# HUD-mohterboard.net
KiCad netlist of a schematic drawn in EAGLE
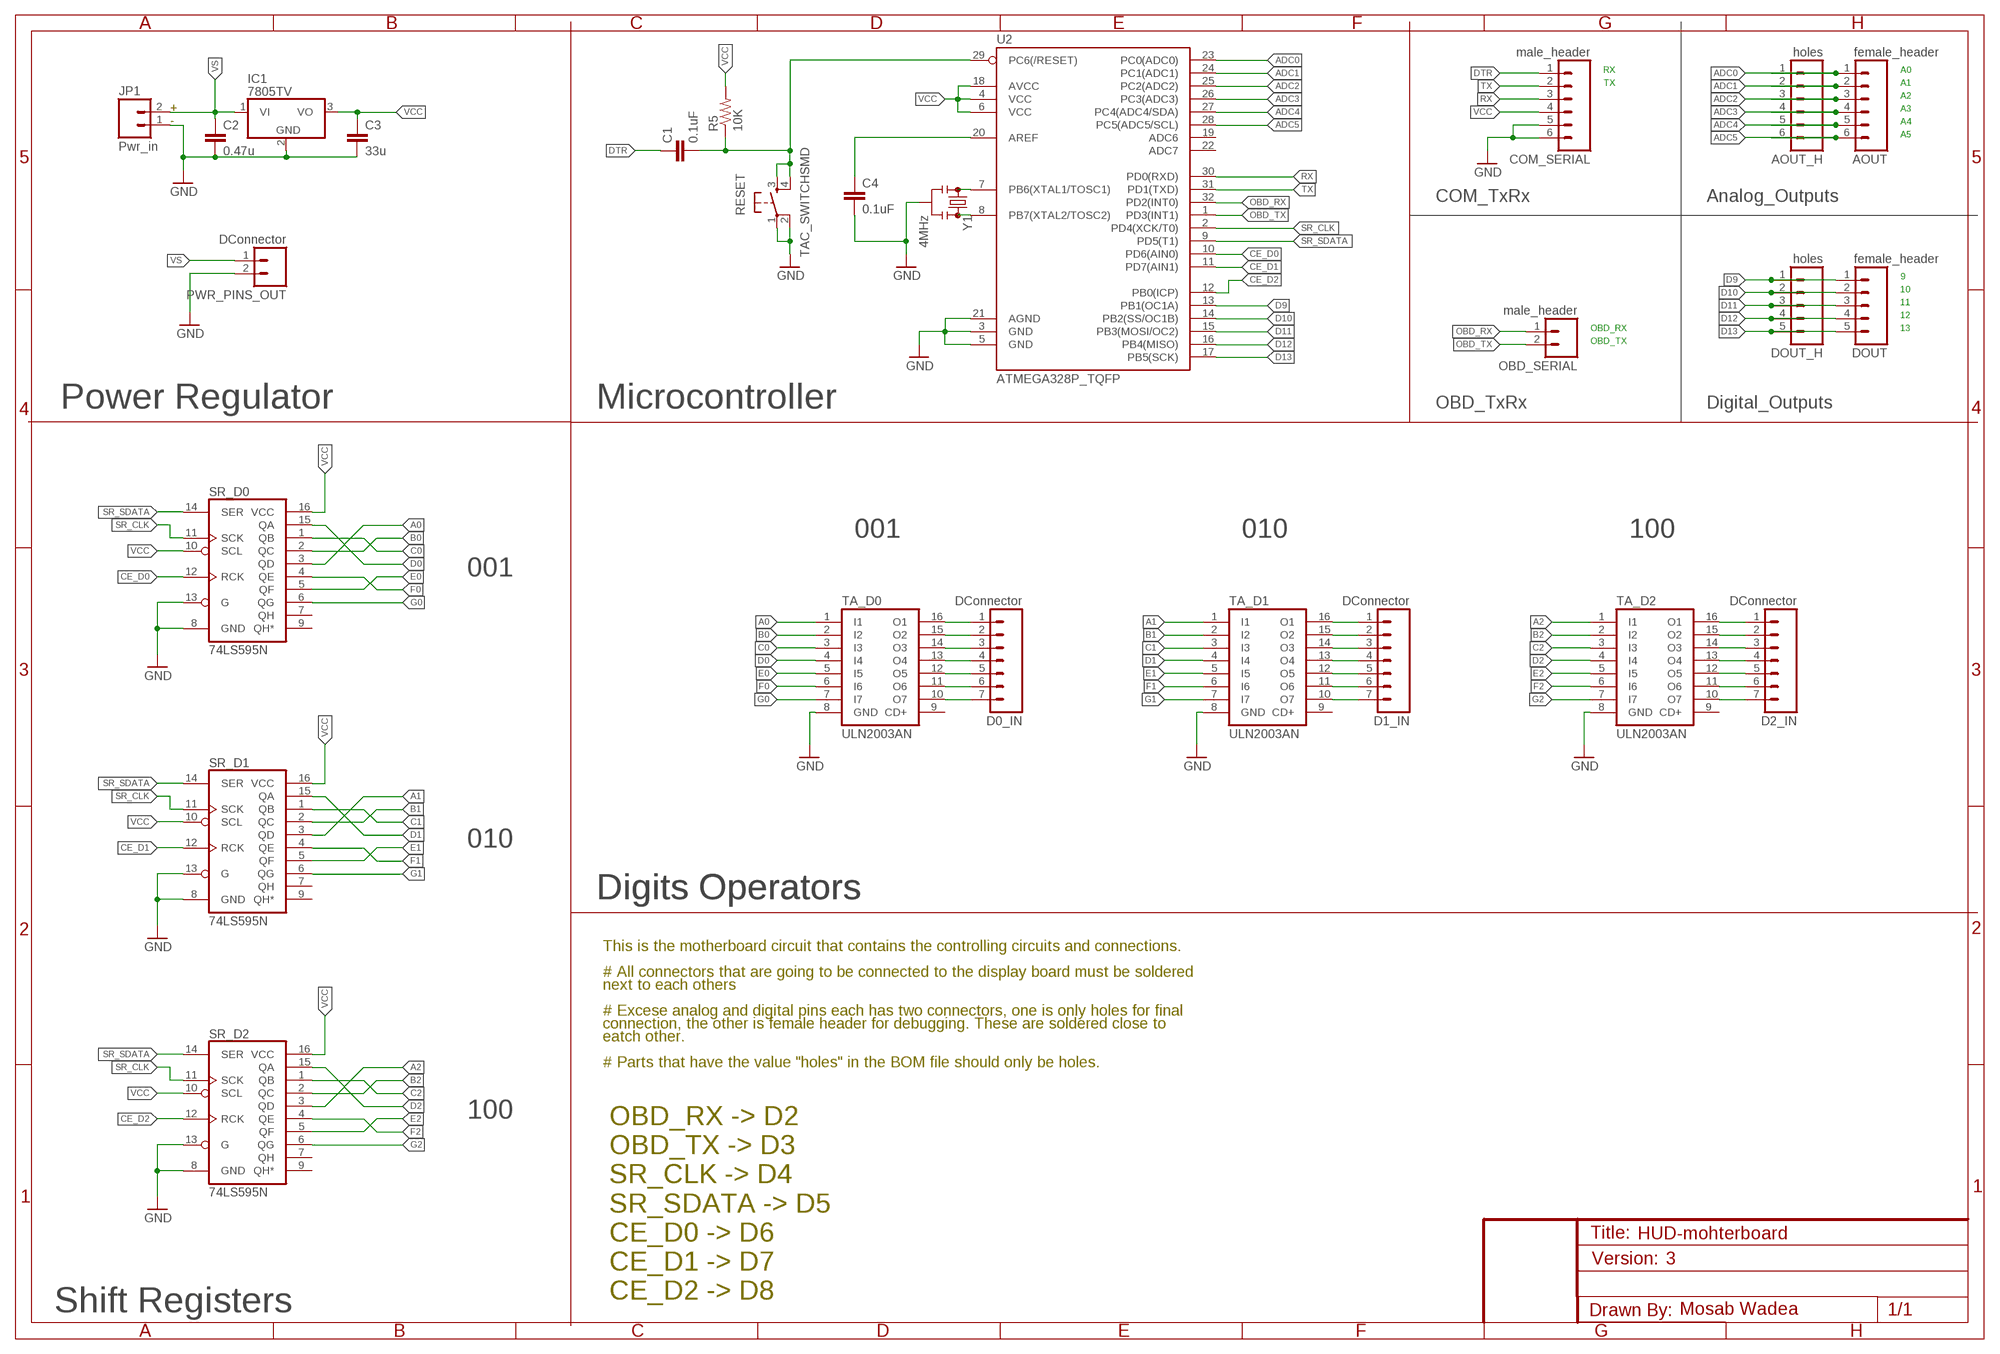
[diagram p0: schematic, sheet 1]

(export (version "E")
  (design (tool "Eeschema 10.0.6"))
  (components
    (comp (ref "AOUT")
      (value "female_header")
      (footprint "eagle-import:1X06")
      (libsource (lib "eagle-import") (part "M06SILK_FEMALE_PTH"))
    )
    (comp (ref "AOUT_H")
      (value "holes")
      (footprint "eagle-import:1X06")
      (libsource (lib "eagle-import") (part "M06SILK_FEMALE_PTH"))
    )
    (comp (ref "C1")
      (value "0.1uF")
      (footprint "eagle-import:0805")
      (libsource (lib "eagle-import") (part "CAP0805"))
    )
    (comp (ref "C2")
      (value "0.47u")
      (footprint "eagle-import:0805")
      (libsource (lib "eagle-import") (part "CAP0805"))
    )
    (comp (ref "C3")
      (value "33u")
      (footprint "eagle-import:0805")
      (libsource (lib "eagle-import") (part "CAP0805"))
    )
    (comp (ref "C4")
      (value "0.1uF")
      (footprint "eagle-import:0805")
      (libsource (lib "eagle-import") (part "CAP0805"))
    )
    (comp (ref "COM_SERIAL")
      (value "male_header")
      (footprint "eagle-import:1X06")
      (libsource (lib "eagle-import") (part "M06SILK_FEMALE_PTH"))
    )
    (comp (ref "D0_IN")
      (value "DConnector")
      (footprint "eagle-import:1X07")
      (libsource (lib "eagle-import") (part "M07"))
    )
    (comp (ref "D1_IN")
      (value "DConnector")
      (footprint "eagle-import:1X07")
      (libsource (lib "eagle-import") (part "M07"))
    )
    (comp (ref "D2_IN")
      (value "DConnector")
      (footprint "eagle-import:1X07")
      (libsource (lib "eagle-import") (part "M07"))
    )
    (comp (ref "DOUT")
      (value "female_header")
      (footprint "eagle-import:1X05")
      (libsource (lib "eagle-import") (part "M05PTH"))
    )
    (comp (ref "DOUT_H")
      (value "holes")
      (footprint "eagle-import:1X05")
      (libsource (lib "eagle-import") (part "M05PTH"))
    )
    (comp (ref "IC1")
      (value "7805TV")
      (footprint "eagle-import:TO220V")
      (libsource (lib "eagle-import") (part "78TV05"))
    )
    (comp (ref "JP1")
      (value "Pwr_in")
      (footprint "eagle-import:1X02")
      (libsource (lib "eagle-import") (part "M02PTH"))
    )
    (comp (ref "OBD_SERIAL")
      (value "male_header")
      (footprint "eagle-import:1X02")
      (libsource (lib "eagle-import") (part "M02PTH"))
    )
    (comp (ref "PWR_PINS_OUT")
      (value "DConnector")
      (footprint "eagle-import:1X02")
      (libsource (lib "eagle-import") (part "M02PTH"))
    )
    (comp (ref "R5")
      (value "10K")
      (footprint "eagle-import:0805")
      (libsource (lib "eagle-import") (part "RESISTOR0805-RES"))
    )
    (comp (ref "RESET")
      (value "TAC_SWITCHSMD")
      (footprint "eagle-import:TACTILE-SWITCH-SMD")
      (libsource (lib "eagle-import") (part "TAC_SWITCHSMD"))
    )
    (comp (ref "SR_D0")
      (value "74LS595N")
      (footprint "eagle-import:DIL16")
      (libsource (lib "eagle-import") (part "74595NLS"))
    )
    (comp (ref "SR_D1")
      (value "74LS595N")
      (footprint "eagle-import:DIL16")
      (libsource (lib "eagle-import") (part "74595NLS"))
    )
    (comp (ref "SR_D2")
      (value "74LS595N")
      (footprint "eagle-import:DIL16")
      (libsource (lib "eagle-import") (part "74595NLS"))
    )
    (comp (ref "TA_D0")
      (value "ULN2003AN")
      (footprint "eagle-import:DIL16")
      (libsource (lib "eagle-import") (part "ULN2003AN"))
    )
    (comp (ref "TA_D1")
      (value "ULN2003AN")
      (footprint "eagle-import:DIL16")
      (libsource (lib "eagle-import") (part "ULN2003AN"))
    )
    (comp (ref "TA_D2")
      (value "ULN2003AN")
      (footprint "eagle-import:DIL16")
      (libsource (lib "eagle-import") (part "ULN2003AN"))
    )
    (comp (ref "U2")
      (value "ATMEGA328P_TQFP")
      (footprint "eagle-import:TQFP32-08")
      (libsource (lib "eagle-import") (part "ATMEGA328P_TQFP"))
    )
    (comp (ref "Y1")
      (value "4MHz")
      (footprint "eagle-import:RESONATOR-SMD_MED")
      (libsource (lib "eagle-import") (part "RESONATOR4MHZ"))
    )
  )
  (nets
    (net (code "1") (name "A0") (class "Default")
      (node (ref "SR_D0") (pin "3") (pinfunction "QD_3") (pintype "tri_state"))
      (node (ref "TA_D0") (pin "1") (pinfunction "I1_1") (pintype "input"))
    )
    (net (code "2") (name "A1") (class "Default")
      (node (ref "SR_D1") (pin "3") (pinfunction "QD_3") (pintype "tri_state"))
      (node (ref "TA_D1") (pin "1") (pinfunction "I1_1") (pintype "input"))
    )
    (net (code "3") (name "A2") (class "Default")
      (node (ref "SR_D2") (pin "3") (pinfunction "QD_3") (pintype "tri_state"))
      (node (ref "TA_D2") (pin "1") (pinfunction "I1_1") (pintype "input"))
    )
    (net (code "4") (name "ADC0") (class "Default")
      (node (ref "AOUT") (pin "1") (pinfunction "1_1") (pintype "passive"))
      (node (ref "AOUT_H") (pin "1") (pinfunction "1_1") (pintype "passive"))
      (node (ref "U2") (pin "23") (pinfunction "PC0(ADC0)_23") (pintype "bidirectional"))
    )
    (net (code "5") (name "ADC1") (class "Default")
      (node (ref "AOUT") (pin "2") (pinfunction "2_2") (pintype "passive"))
      (node (ref "AOUT_H") (pin "2") (pinfunction "2_2") (pintype "passive"))
      (node (ref "U2") (pin "24") (pinfunction "PC1(ADC1)_24") (pintype "bidirectional"))
    )
    (net (code "6") (name "ADC2") (class "Default")
      (node (ref "AOUT") (pin "3") (pinfunction "3_3") (pintype "passive"))
      (node (ref "AOUT_H") (pin "3") (pinfunction "3_3") (pintype "passive"))
      (node (ref "U2") (pin "25") (pinfunction "PC2(ADC2)_25") (pintype "bidirectional"))
    )
    (net (code "7") (name "ADC3") (class "Default")
      (node (ref "AOUT") (pin "4") (pinfunction "4_4") (pintype "passive"))
      (node (ref "AOUT_H") (pin "4") (pinfunction "4_4") (pintype "passive"))
      (node (ref "U2") (pin "26") (pinfunction "PC3(ADC3)_26") (pintype "bidirectional"))
    )
    (net (code "8") (name "ADC4") (class "Default")
      (node (ref "AOUT") (pin "5") (pinfunction "5_5") (pintype "passive"))
      (node (ref "AOUT_H") (pin "5") (pinfunction "5_5") (pintype "passive"))
      (node (ref "U2") (pin "27") (pinfunction "PC4(ADC4/SDA)_27") (pintype "bidirectional"))
    )
    (net (code "9") (name "ADC5") (class "Default")
      (node (ref "AOUT") (pin "6") (pinfunction "6_6") (pintype "passive"))
      (node (ref "AOUT_H") (pin "6") (pinfunction "6_6") (pintype "passive"))
      (node (ref "U2") (pin "28") (pinfunction "PC5(ADC5/SCL)_28") (pintype "bidirectional"))
    )
    (net (code "10") (name "B0") (class "Default")
      (node (ref "SR_D0") (pin "2") (pinfunction "QC_2") (pintype "tri_state"))
      (node (ref "TA_D0") (pin "2") (pinfunction "I2_2") (pintype "input"))
    )
    (net (code "11") (name "B1") (class "Default")
      (node (ref "SR_D1") (pin "2") (pinfunction "QC_2") (pintype "tri_state"))
      (node (ref "TA_D1") (pin "2") (pinfunction "I2_2") (pintype "input"))
    )
    (net (code "12") (name "B2") (class "Default")
      (node (ref "SR_D2") (pin "2") (pinfunction "QC_2") (pintype "tri_state"))
      (node (ref "TA_D2") (pin "2") (pinfunction "I2_2") (pintype "input"))
    )
    (net (code "13") (name "C0") (class "Default")
      (node (ref "SR_D0") (pin "1") (pinfunction "QB_1") (pintype "tri_state"))
      (node (ref "TA_D0") (pin "3") (pinfunction "I3_3") (pintype "input"))
    )
    (net (code "14") (name "C1") (class "Default")
      (node (ref "SR_D1") (pin "1") (pinfunction "QB_1") (pintype "tri_state"))
      (node (ref "TA_D1") (pin "3") (pinfunction "I3_3") (pintype "input"))
    )
    (net (code "15") (name "C2") (class "Default")
      (node (ref "SR_D2") (pin "1") (pinfunction "QB_1") (pintype "tri_state"))
      (node (ref "TA_D2") (pin "3") (pinfunction "I3_3") (pintype "input"))
    )
    (net (code "16") (name "CE_D0") (class "Default")
      (node (ref "SR_D0") (pin "12") (pinfunction "RCK_12") (pintype "input"))
      (node (ref "U2") (pin "10") (pinfunction "PD6(AIN0)_10") (pintype "bidirectional"))
    )
    (net (code "17") (name "CE_D1") (class "Default")
      (node (ref "SR_D1") (pin "12") (pinfunction "RCK_12") (pintype "input"))
      (node (ref "U2") (pin "11") (pinfunction "PD7(AIN1)_11") (pintype "bidirectional"))
    )
    (net (code "18") (name "CE_D2") (class "Default")
      (node (ref "SR_D2") (pin "12") (pinfunction "RCK_12") (pintype "input"))
      (node (ref "U2") (pin "12") (pinfunction "PB0(ICP)_12") (pintype "bidirectional"))
    )
    (net (code "19") (name "D0") (class "Default")
      (node (ref "SR_D0") (pin "15") (pinfunction "QA_15") (pintype "tri_state"))
      (node (ref "TA_D0") (pin "4") (pinfunction "I4_4") (pintype "input"))
    )
    (net (code "20") (name "D1") (class "Default")
      (node (ref "SR_D1") (pin "15") (pinfunction "QA_15") (pintype "tri_state"))
      (node (ref "TA_D1") (pin "4") (pinfunction "I4_4") (pintype "input"))
    )
    (net (code "21") (name "D2") (class "Default")
      (node (ref "SR_D2") (pin "15") (pinfunction "QA_15") (pintype "tri_state"))
      (node (ref "TA_D2") (pin "4") (pinfunction "I4_4") (pintype "input"))
    )
    (net (code "22") (name "D9") (class "Default")
      (node (ref "DOUT") (pin "1") (pinfunction "1_1") (pintype "passive"))
      (node (ref "DOUT_H") (pin "1") (pinfunction "1_1") (pintype "passive"))
      (node (ref "U2") (pin "13") (pinfunction "PB1(OC1A)_13") (pintype "bidirectional"))
    )
    (net (code "23") (name "D10") (class "Default")
      (node (ref "DOUT") (pin "2") (pinfunction "2_2") (pintype "passive"))
      (node (ref "DOUT_H") (pin "2") (pinfunction "2_2") (pintype "passive"))
      (node (ref "U2") (pin "14") (pinfunction "PB2(SS/OC1B)_14") (pintype "bidirectional"))
    )
    (net (code "24") (name "D11") (class "Default")
      (node (ref "DOUT") (pin "3") (pinfunction "3_3") (pintype "passive"))
      (node (ref "DOUT_H") (pin "3") (pinfunction "3_3") (pintype "passive"))
      (node (ref "U2") (pin "15") (pinfunction "PB3(MOSI/OC2)_15") (pintype "bidirectional"))
    )
    (net (code "25") (name "D12") (class "Default")
      (node (ref "DOUT") (pin "4") (pinfunction "4_4") (pintype "passive"))
      (node (ref "DOUT_H") (pin "4") (pinfunction "4_4") (pintype "passive"))
      (node (ref "U2") (pin "16") (pinfunction "PB4(MISO)_16") (pintype "bidirectional"))
    )
    (net (code "26") (name "D13") (class "Default")
      (node (ref "DOUT") (pin "5") (pinfunction "5_5") (pintype "passive"))
      (node (ref "DOUT_H") (pin "5") (pinfunction "5_5") (pintype "passive"))
      (node (ref "U2") (pin "17") (pinfunction "PB5(SCK)_17") (pintype "bidirectional"))
    )
    (net (code "27") (name "DTR") (class "Default")
      (node (ref "C1") (pin "1") (pinfunction "1_1") (pintype "passive"))
      (node (ref "COM_SERIAL") (pin "1") (pinfunction "1_1") (pintype "passive"))
    )
    (net (code "28") (name "E0") (class "Default")
      (node (ref "SR_D0") (pin "5") (pinfunction "QF_5") (pintype "tri_state"))
      (node (ref "TA_D0") (pin "5") (pinfunction "I5_5") (pintype "input"))
    )
    (net (code "29") (name "E1") (class "Default")
      (node (ref "SR_D1") (pin "5") (pinfunction "QF_5") (pintype "tri_state"))
      (node (ref "TA_D1") (pin "5") (pinfunction "I5_5") (pintype "input"))
    )
    (net (code "30") (name "E2") (class "Default")
      (node (ref "SR_D2") (pin "5") (pinfunction "QF_5") (pintype "tri_state"))
      (node (ref "TA_D2") (pin "5") (pinfunction "I5_5") (pintype "input"))
    )
    (net (code "31") (name "F0") (class "Default")
      (node (ref "SR_D0") (pin "4") (pinfunction "QE_4") (pintype "tri_state"))
      (node (ref "TA_D0") (pin "6") (pinfunction "I6_6") (pintype "input"))
    )
    (net (code "32") (name "F1") (class "Default")
      (node (ref "SR_D1") (pin "4") (pinfunction "QE_4") (pintype "tri_state"))
      (node (ref "TA_D1") (pin "6") (pinfunction "I6_6") (pintype "input"))
    )
    (net (code "33") (name "F2") (class "Default")
      (node (ref "SR_D2") (pin "4") (pinfunction "QE_4") (pintype "tri_state"))
      (node (ref "TA_D2") (pin "6") (pinfunction "I6_6") (pintype "input"))
    )
    (net (code "34") (name "G0") (class "Default")
      (node (ref "SR_D0") (pin "6") (pinfunction "QG_6") (pintype "tri_state"))
      (node (ref "TA_D0") (pin "7") (pinfunction "I7_7") (pintype "input"))
    )
    (net (code "35") (name "G1") (class "Default")
      (node (ref "SR_D1") (pin "6") (pinfunction "QG_6") (pintype "tri_state"))
      (node (ref "TA_D1") (pin "7") (pinfunction "I7_7") (pintype "input"))
    )
    (net (code "36") (name "G2") (class "Default")
      (node (ref "SR_D2") (pin "6") (pinfunction "QG_6") (pintype "tri_state"))
      (node (ref "TA_D2") (pin "7") (pinfunction "I7_7") (pintype "input"))
    )
    (net (code "37") (name "GND") (class "Default")
      (node (ref "C2") (pin "2") (pinfunction "2_2") (pintype "passive"))
      (node (ref "C3") (pin "2") (pinfunction "2_2") (pintype "passive"))
      (node (ref "C4") (pin "2") (pinfunction "2_2") (pintype "passive"))
      (node (ref "COM_SERIAL") (pin "5") (pinfunction "5_5") (pintype "passive"))
      (node (ref "COM_SERIAL") (pin "6") (pinfunction "6_6") (pintype "passive"))
      (node (ref "IC1") (pin "2") (pinfunction "GND_2") (pintype "passive"))
      (node (ref "JP1") (pin "1") (pinfunction "1_1") (pintype "passive"))
      (node (ref "PWR_PINS_OUT") (pin "2") (pinfunction "2_2") (pintype "passive"))
      (node (ref "RESET") (pin "1") (pinfunction "1_1") (pintype "passive"))
      (node (ref "RESET") (pin "2") (pinfunction "2_2") (pintype "passive"))
      (node (ref "SR_D0") (pin "13") (pinfunction "G_13") (pintype "input"))
      (node (ref "SR_D0") (pin "8") (pinfunction "GND_8") (pintype "power_in"))
      (node (ref "SR_D1") (pin "13") (pinfunction "G_13") (pintype "input"))
      (node (ref "SR_D1") (pin "8") (pinfunction "GND_8") (pintype "power_in"))
      (node (ref "SR_D2") (pin "13") (pinfunction "G_13") (pintype "input"))
      (node (ref "SR_D2") (pin "8") (pinfunction "GND_8") (pintype "power_in"))
      (node (ref "TA_D0") (pin "8") (pinfunction "GND_8") (pintype "power_in"))
      (node (ref "TA_D1") (pin "8") (pinfunction "GND_8") (pintype "power_in"))
      (node (ref "TA_D2") (pin "8") (pinfunction "GND_8") (pintype "power_in"))
      (node (ref "U2") (pin "21") (pinfunction "AGND_21") (pintype "bidirectional"))
      (node (ref "U2") (pin "3") (pinfunction "GND_3") (pintype "bidirectional"))
      (node (ref "U2") (pin "5") (pinfunction "GND_5") (pintype "bidirectional"))
      (node (ref "Y1") (pin "2") (pinfunction "2_2") (pintype "passive"))
    )
    (net (code "38") (name "Net-(TA_D0-O1)") (class "Default")
      (node (ref "D0_IN") (pin "1") (pinfunction "1_1") (pintype "passive"))
      (node (ref "TA_D0") (pin "16") (pinfunction "O1_16") (pintype "open_collector"))
    )
    (net (code "39") (name "Net-(TA_D0-O2)") (class "Default")
      (node (ref "D0_IN") (pin "2") (pinfunction "2_2") (pintype "passive"))
      (node (ref "TA_D0") (pin "15") (pinfunction "O2_15") (pintype "open_collector"))
    )
    (net (code "40") (name "Net-(TA_D0-O3)") (class "Default")
      (node (ref "D0_IN") (pin "3") (pinfunction "3_3") (pintype "passive"))
      (node (ref "TA_D0") (pin "14") (pinfunction "O3_14") (pintype "open_collector"))
    )
    (net (code "41") (name "Net-(TA_D0-O4)") (class "Default")
      (node (ref "D0_IN") (pin "4") (pinfunction "4_4") (pintype "passive"))
      (node (ref "TA_D0") (pin "13") (pinfunction "O4_13") (pintype "open_collector"))
    )
    (net (code "42") (name "Net-(TA_D0-O5)") (class "Default")
      (node (ref "D0_IN") (pin "5") (pinfunction "5_5") (pintype "passive"))
      (node (ref "TA_D0") (pin "12") (pinfunction "O5_12") (pintype "open_collector"))
    )
    (net (code "43") (name "Net-(TA_D0-O6)") (class "Default")
      (node (ref "D0_IN") (pin "6") (pinfunction "6_6") (pintype "passive"))
      (node (ref "TA_D0") (pin "11") (pinfunction "O6_11") (pintype "open_collector"))
    )
    (net (code "44") (name "Net-(TA_D0-O7)") (class "Default")
      (node (ref "D0_IN") (pin "7") (pinfunction "7_7") (pintype "passive"))
      (node (ref "TA_D0") (pin "10") (pinfunction "O7_10") (pintype "open_collector"))
    )
    (net (code "45") (name "Net-(TA_D1-O1)") (class "Default")
      (node (ref "D1_IN") (pin "1") (pinfunction "1_1") (pintype "passive"))
      (node (ref "TA_D1") (pin "16") (pinfunction "O1_16") (pintype "open_collector"))
    )
    (net (code "46") (name "Net-(TA_D1-O2)") (class "Default")
      (node (ref "D1_IN") (pin "2") (pinfunction "2_2") (pintype "passive"))
      (node (ref "TA_D1") (pin "15") (pinfunction "O2_15") (pintype "open_collector"))
    )
    (net (code "47") (name "Net-(TA_D1-O3)") (class "Default")
      (node (ref "D1_IN") (pin "3") (pinfunction "3_3") (pintype "passive"))
      (node (ref "TA_D1") (pin "14") (pinfunction "O3_14") (pintype "open_collector"))
    )
    (net (code "48") (name "Net-(TA_D1-O4)") (class "Default")
      (node (ref "D1_IN") (pin "4") (pinfunction "4_4") (pintype "passive"))
      (node (ref "TA_D1") (pin "13") (pinfunction "O4_13") (pintype "open_collector"))
    )
    (net (code "49") (name "Net-(TA_D1-O5)") (class "Default")
      (node (ref "D1_IN") (pin "5") (pinfunction "5_5") (pintype "passive"))
      (node (ref "TA_D1") (pin "12") (pinfunction "O5_12") (pintype "open_collector"))
    )
    (net (code "50") (name "Net-(TA_D1-O6)") (class "Default")
      (node (ref "D1_IN") (pin "6") (pinfunction "6_6") (pintype "passive"))
      (node (ref "TA_D1") (pin "11") (pinfunction "O6_11") (pintype "open_collector"))
    )
    (net (code "51") (name "Net-(TA_D1-O7)") (class "Default")
      (node (ref "D1_IN") (pin "7") (pinfunction "7_7") (pintype "passive"))
      (node (ref "TA_D1") (pin "10") (pinfunction "O7_10") (pintype "open_collector"))
    )
    (net (code "52") (name "Net-(TA_D2-O1)") (class "Default")
      (node (ref "D2_IN") (pin "1") (pinfunction "1_1") (pintype "passive"))
      (node (ref "TA_D2") (pin "16") (pinfunction "O1_16") (pintype "open_collector"))
    )
    (net (code "53") (name "Net-(TA_D2-O2)") (class "Default")
      (node (ref "D2_IN") (pin "2") (pinfunction "2_2") (pintype "passive"))
      (node (ref "TA_D2") (pin "15") (pinfunction "O2_15") (pintype "open_collector"))
    )
    (net (code "54") (name "Net-(TA_D2-O3)") (class "Default")
      (node (ref "D2_IN") (pin "3") (pinfunction "3_3") (pintype "passive"))
      (node (ref "TA_D2") (pin "14") (pinfunction "O3_14") (pintype "open_collector"))
    )
    (net (code "55") (name "Net-(TA_D2-O4)") (class "Default")
      (node (ref "D2_IN") (pin "4") (pinfunction "4_4") (pintype "passive"))
      (node (ref "TA_D2") (pin "13") (pinfunction "O4_13") (pintype "open_collector"))
    )
    (net (code "56") (name "Net-(TA_D2-O5)") (class "Default")
      (node (ref "D2_IN") (pin "5") (pinfunction "5_5") (pintype "passive"))
      (node (ref "TA_D2") (pin "12") (pinfunction "O5_12") (pintype "open_collector"))
    )
    (net (code "57") (name "Net-(TA_D2-O6)") (class "Default")
      (node (ref "D2_IN") (pin "6") (pinfunction "6_6") (pintype "passive"))
      (node (ref "TA_D2") (pin "11") (pinfunction "O6_11") (pintype "open_collector"))
    )
    (net (code "58") (name "Net-(TA_D2-O7)") (class "Default")
      (node (ref "D2_IN") (pin "7") (pinfunction "7_7") (pintype "passive"))
      (node (ref "TA_D2") (pin "10") (pinfunction "O7_10") (pintype "open_collector"))
    )
    (net (code "59") (name "Net-(U2-AREF)") (class "Default")
      (node (ref "C4") (pin "1") (pinfunction "1_1") (pintype "passive"))
      (node (ref "U2") (pin "20") (pinfunction "AREF_20") (pintype "bidirectional"))
    )
    (net (code "60") (name "Net-(U2-PB6(XTAL1{slash}TOSC1))") (class "Default")
      (node (ref "U2") (pin "7") (pinfunction "PB6(XTAL1/TOSC1)_7") (pintype "bidirectional"))
      (node (ref "Y1") (pin "1") (pinfunction "1_1") (pintype "passive"))
    )
    (net (code "61") (name "Net-(U2-PB7(XTAL2{slash}TOSC2))") (class "Default")
      (node (ref "U2") (pin "8") (pinfunction "PB7(XTAL2/TOSC2)_8") (pintype "bidirectional"))
      (node (ref "Y1") (pin "3") (pinfunction "3_3") (pintype "passive"))
    )
    (net (code "62") (name "Net-(U2-PC6({slash}RESET))") (class "Default")
      (node (ref "C1") (pin "2") (pinfunction "2_2") (pintype "passive"))
      (node (ref "R5") (pin "1") (pinfunction "1_1") (pintype "passive"))
      (node (ref "RESET") (pin "3") (pinfunction "3_3") (pintype "passive"))
      (node (ref "RESET") (pin "4") (pinfunction "4_4") (pintype "passive"))
      (node (ref "U2") (pin "29") (pinfunction "PC6(/RESET)_29") (pintype "bidirectional"))
    )
    (net (code "63") (name "OBD_RX") (class "Default")
      (node (ref "OBD_SERIAL") (pin "1") (pinfunction "1_1") (pintype "passive"))
      (node (ref "U2") (pin "32") (pinfunction "PD2(INT0)_32") (pintype "bidirectional"))
    )
    (net (code "64") (name "OBD_TX") (class "Default")
      (node (ref "OBD_SERIAL") (pin "2") (pinfunction "2_2") (pintype "passive"))
      (node (ref "U2") (pin "1") (pinfunction "PD3(INT1)_1") (pintype "bidirectional"))
    )
    (net (code "65") (name "RX") (class "Default")
      (node (ref "COM_SERIAL") (pin "3") (pinfunction "3_3") (pintype "passive"))
      (node (ref "U2") (pin "30") (pinfunction "PD0(RXD)_30") (pintype "bidirectional"))
    )
    (net (code "66") (name "SR_CLK") (class "Default")
      (node (ref "SR_D0") (pin "11") (pinfunction "SCK_11") (pintype "input"))
      (node (ref "SR_D1") (pin "11") (pinfunction "SCK_11") (pintype "input"))
      (node (ref "SR_D2") (pin "11") (pinfunction "SCK_11") (pintype "input"))
      (node (ref "U2") (pin "2") (pinfunction "PD4(XCK/T0)_2") (pintype "bidirectional"))
    )
    (net (code "67") (name "SR_SDATA") (class "Default")
      (node (ref "SR_D0") (pin "14") (pinfunction "SER_14") (pintype "input"))
      (node (ref "SR_D1") (pin "14") (pinfunction "SER_14") (pintype "input"))
      (node (ref "SR_D2") (pin "14") (pinfunction "SER_14") (pintype "input"))
      (node (ref "U2") (pin "9") (pinfunction "PD5(T1)_9") (pintype "bidirectional"))
    )
    (net (code "68") (name "TX") (class "Default")
      (node (ref "COM_SERIAL") (pin "2") (pinfunction "2_2") (pintype "passive"))
      (node (ref "U2") (pin "31") (pinfunction "PD1(TXD)_31") (pintype "bidirectional"))
    )
    (net (code "69") (name "VCC") (class "Default")
      (node (ref "C3") (pin "1") (pinfunction "1_1") (pintype "passive"))
      (node (ref "COM_SERIAL") (pin "4") (pinfunction "4_4") (pintype "passive"))
      (node (ref "IC1") (pin "3") (pinfunction "VO_3") (pintype "passive"))
      (node (ref "R5") (pin "2") (pinfunction "2_2") (pintype "passive"))
      (node (ref "SR_D0") (pin "10") (pinfunction "SCL_10") (pintype "input"))
      (node (ref "SR_D0") (pin "16") (pinfunction "VCC_16") (pintype "power_in"))
      (node (ref "SR_D1") (pin "10") (pinfunction "SCL_10") (pintype "input"))
      (node (ref "SR_D1") (pin "16") (pinfunction "VCC_16") (pintype "power_in"))
      (node (ref "SR_D2") (pin "10") (pinfunction "SCL_10") (pintype "input"))
      (node (ref "SR_D2") (pin "16") (pinfunction "VCC_16") (pintype "power_in"))
      (node (ref "U2") (pin "18") (pinfunction "AVCC_18") (pintype "bidirectional"))
      (node (ref "U2") (pin "4") (pinfunction "VCC_4") (pintype "bidirectional"))
      (node (ref "U2") (pin "6") (pinfunction "VCC_6") (pintype "bidirectional"))
    )
    (net (code "70") (name "VS") (class "Default")
      (node (ref "C2") (pin "1") (pinfunction "1_1") (pintype "passive"))
      (node (ref "IC1") (pin "1") (pinfunction "VI_1") (pintype "input"))
      (node (ref "JP1") (pin "2") (pinfunction "2_2") (pintype "passive"))
      (node (ref "PWR_PINS_OUT") (pin "1") (pinfunction "1_1") (pintype "passive"))
    )
    (net (code "71") (name "unconnected-(SR_D0-QH*-Pad9)") (class "Default")
      (node (ref "SR_D0") (pin "9") (pinfunction "QH*_9") (pintype "tri_state"))
    )
    (net (code "72") (name "unconnected-(SR_D0-QH-Pad7)") (class "Default")
      (node (ref "SR_D0") (pin "7") (pinfunction "QH_7") (pintype "tri_state"))
    )
    (net (code "73") (name "unconnected-(SR_D1-QH*-Pad9)") (class "Default")
      (node (ref "SR_D1") (pin "9") (pinfunction "QH*_9") (pintype "tri_state"))
    )
    (net (code "74") (name "unconnected-(SR_D1-QH-Pad7)") (class "Default")
      (node (ref "SR_D1") (pin "7") (pinfunction "QH_7") (pintype "tri_state"))
    )
    (net (code "75") (name "unconnected-(SR_D2-QH*-Pad9)") (class "Default")
      (node (ref "SR_D2") (pin "9") (pinfunction "QH*_9") (pintype "tri_state"))
    )
    (net (code "76") (name "unconnected-(SR_D2-QH-Pad7)") (class "Default")
      (node (ref "SR_D2") (pin "7") (pinfunction "QH_7") (pintype "tri_state"))
    )
    (net (code "77") (name "unconnected-(TA_D0-CD+-Pad9)") (class "Default")
      (node (ref "TA_D0") (pin "9") (pinfunction "CD+_9") (pintype "passive"))
    )
    (net (code "78") (name "unconnected-(TA_D1-CD+-Pad9)") (class "Default")
      (node (ref "TA_D1") (pin "9") (pinfunction "CD+_9") (pintype "passive"))
    )
    (net (code "79") (name "unconnected-(TA_D2-CD+-Pad9)") (class "Default")
      (node (ref "TA_D2") (pin "9") (pinfunction "CD+_9") (pintype "passive"))
    )
    (net (code "80") (name "unconnected-(U2-ADC6-Pad19)") (class "Default")
      (node (ref "U2") (pin "19") (pinfunction "ADC6_19") (pintype "bidirectional"))
    )
    (net (code "81") (name "unconnected-(U2-ADC7-Pad22)") (class "Default")
      (node (ref "U2") (pin "22") (pinfunction "ADC7_22") (pintype "bidirectional"))
    )
  )
)
